# wisleep_revB.net
KiCad netlist of a schematic drawn in EAGLE
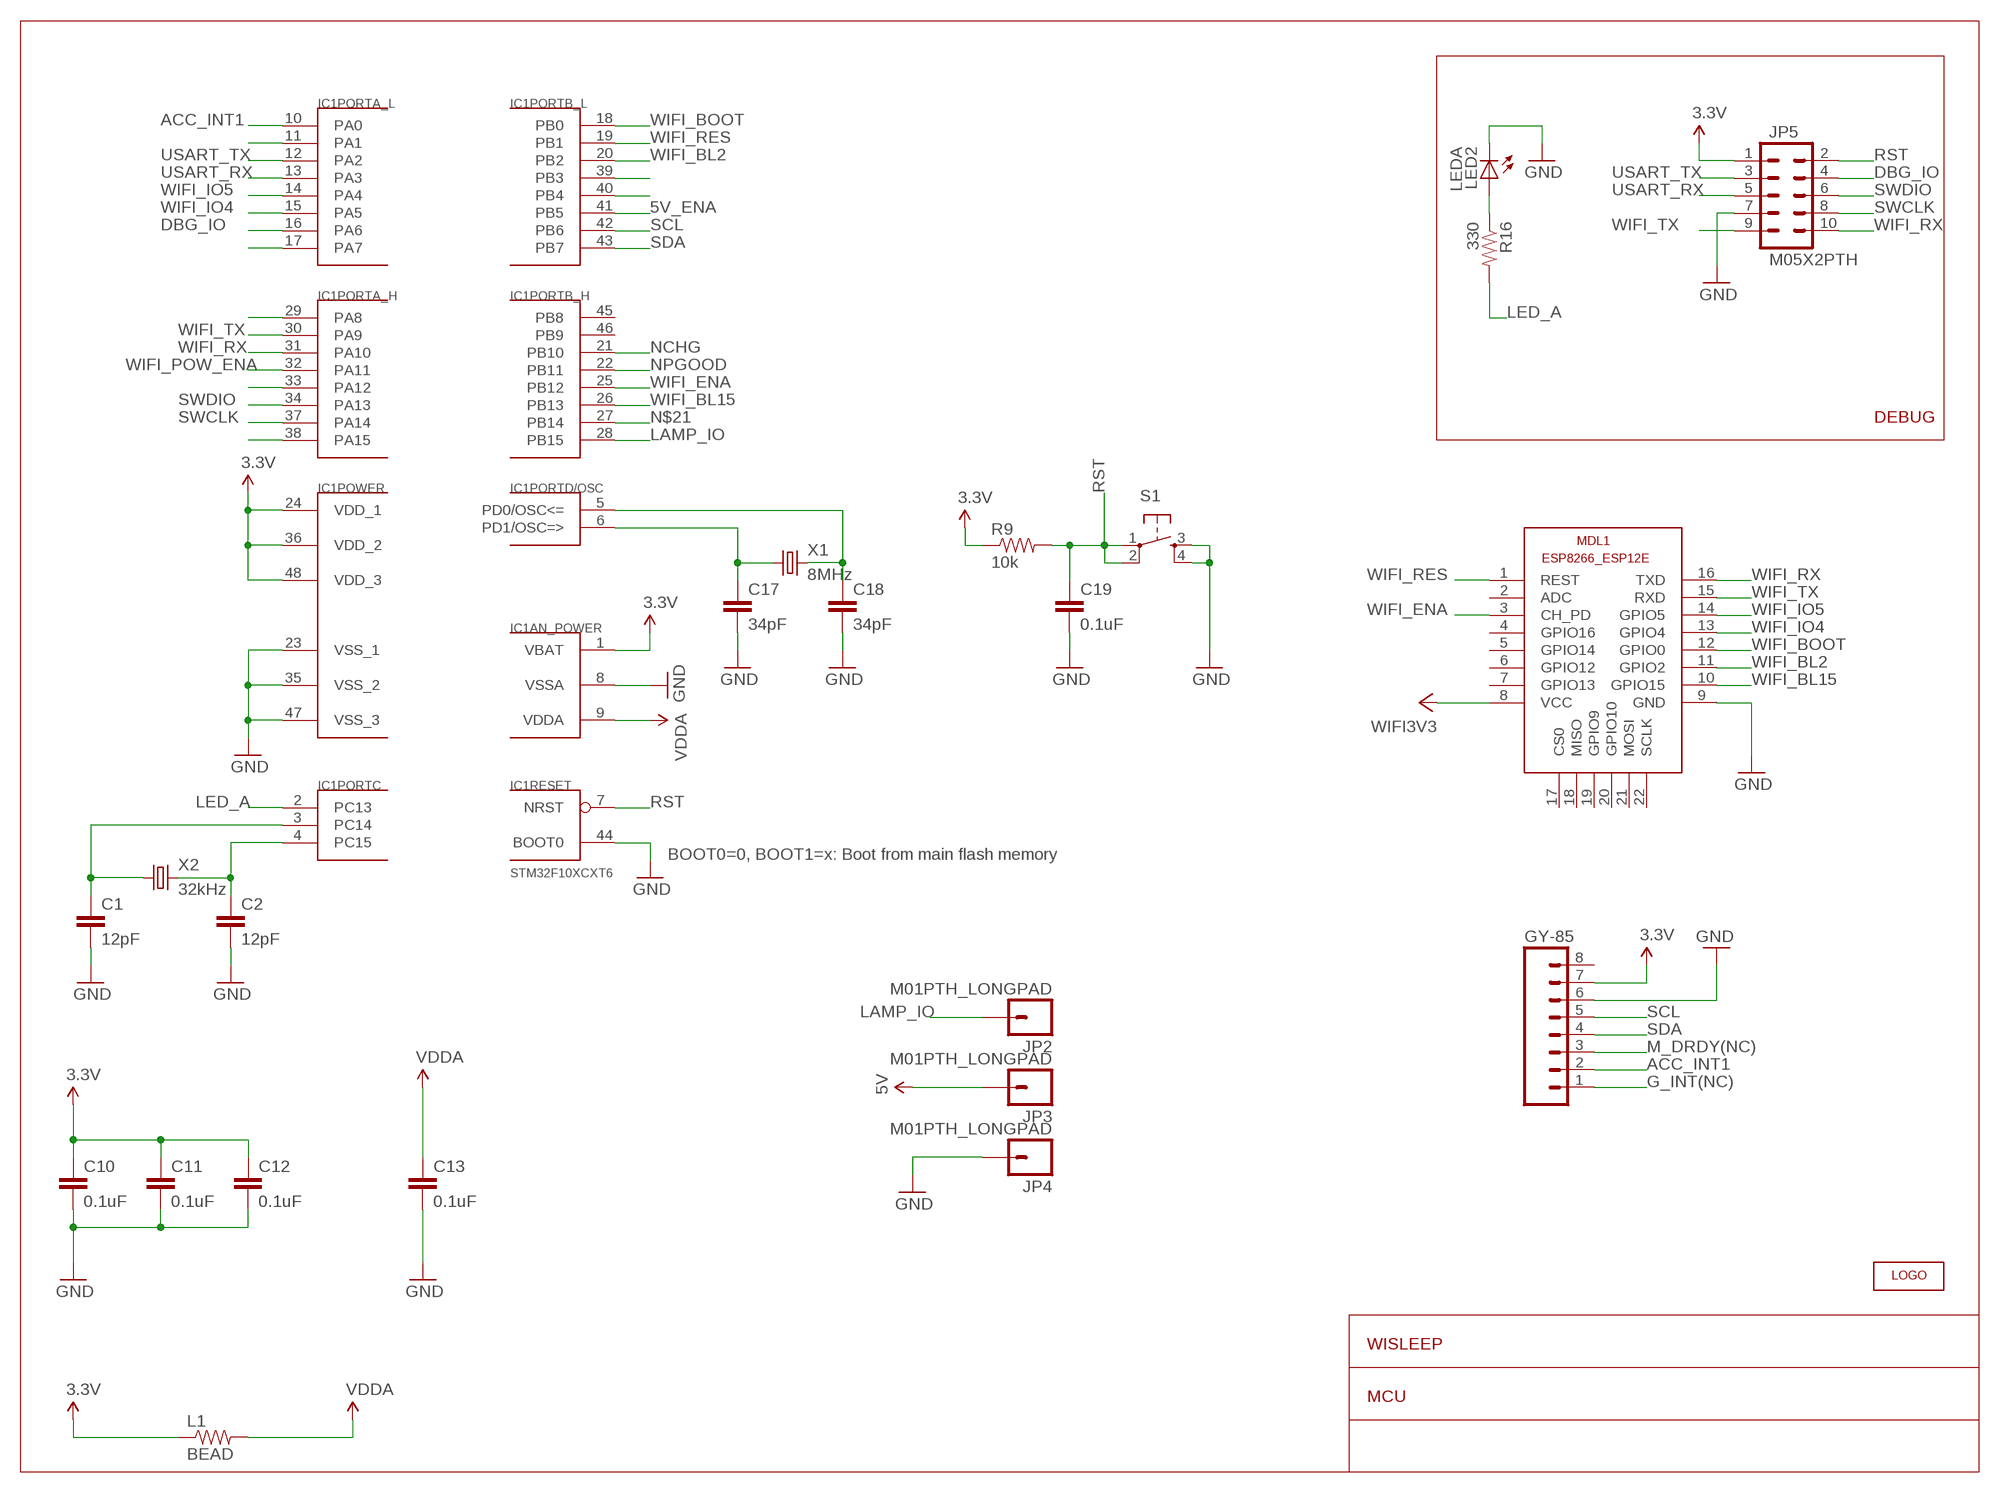
[diagram p0: schematic, sheet 1]
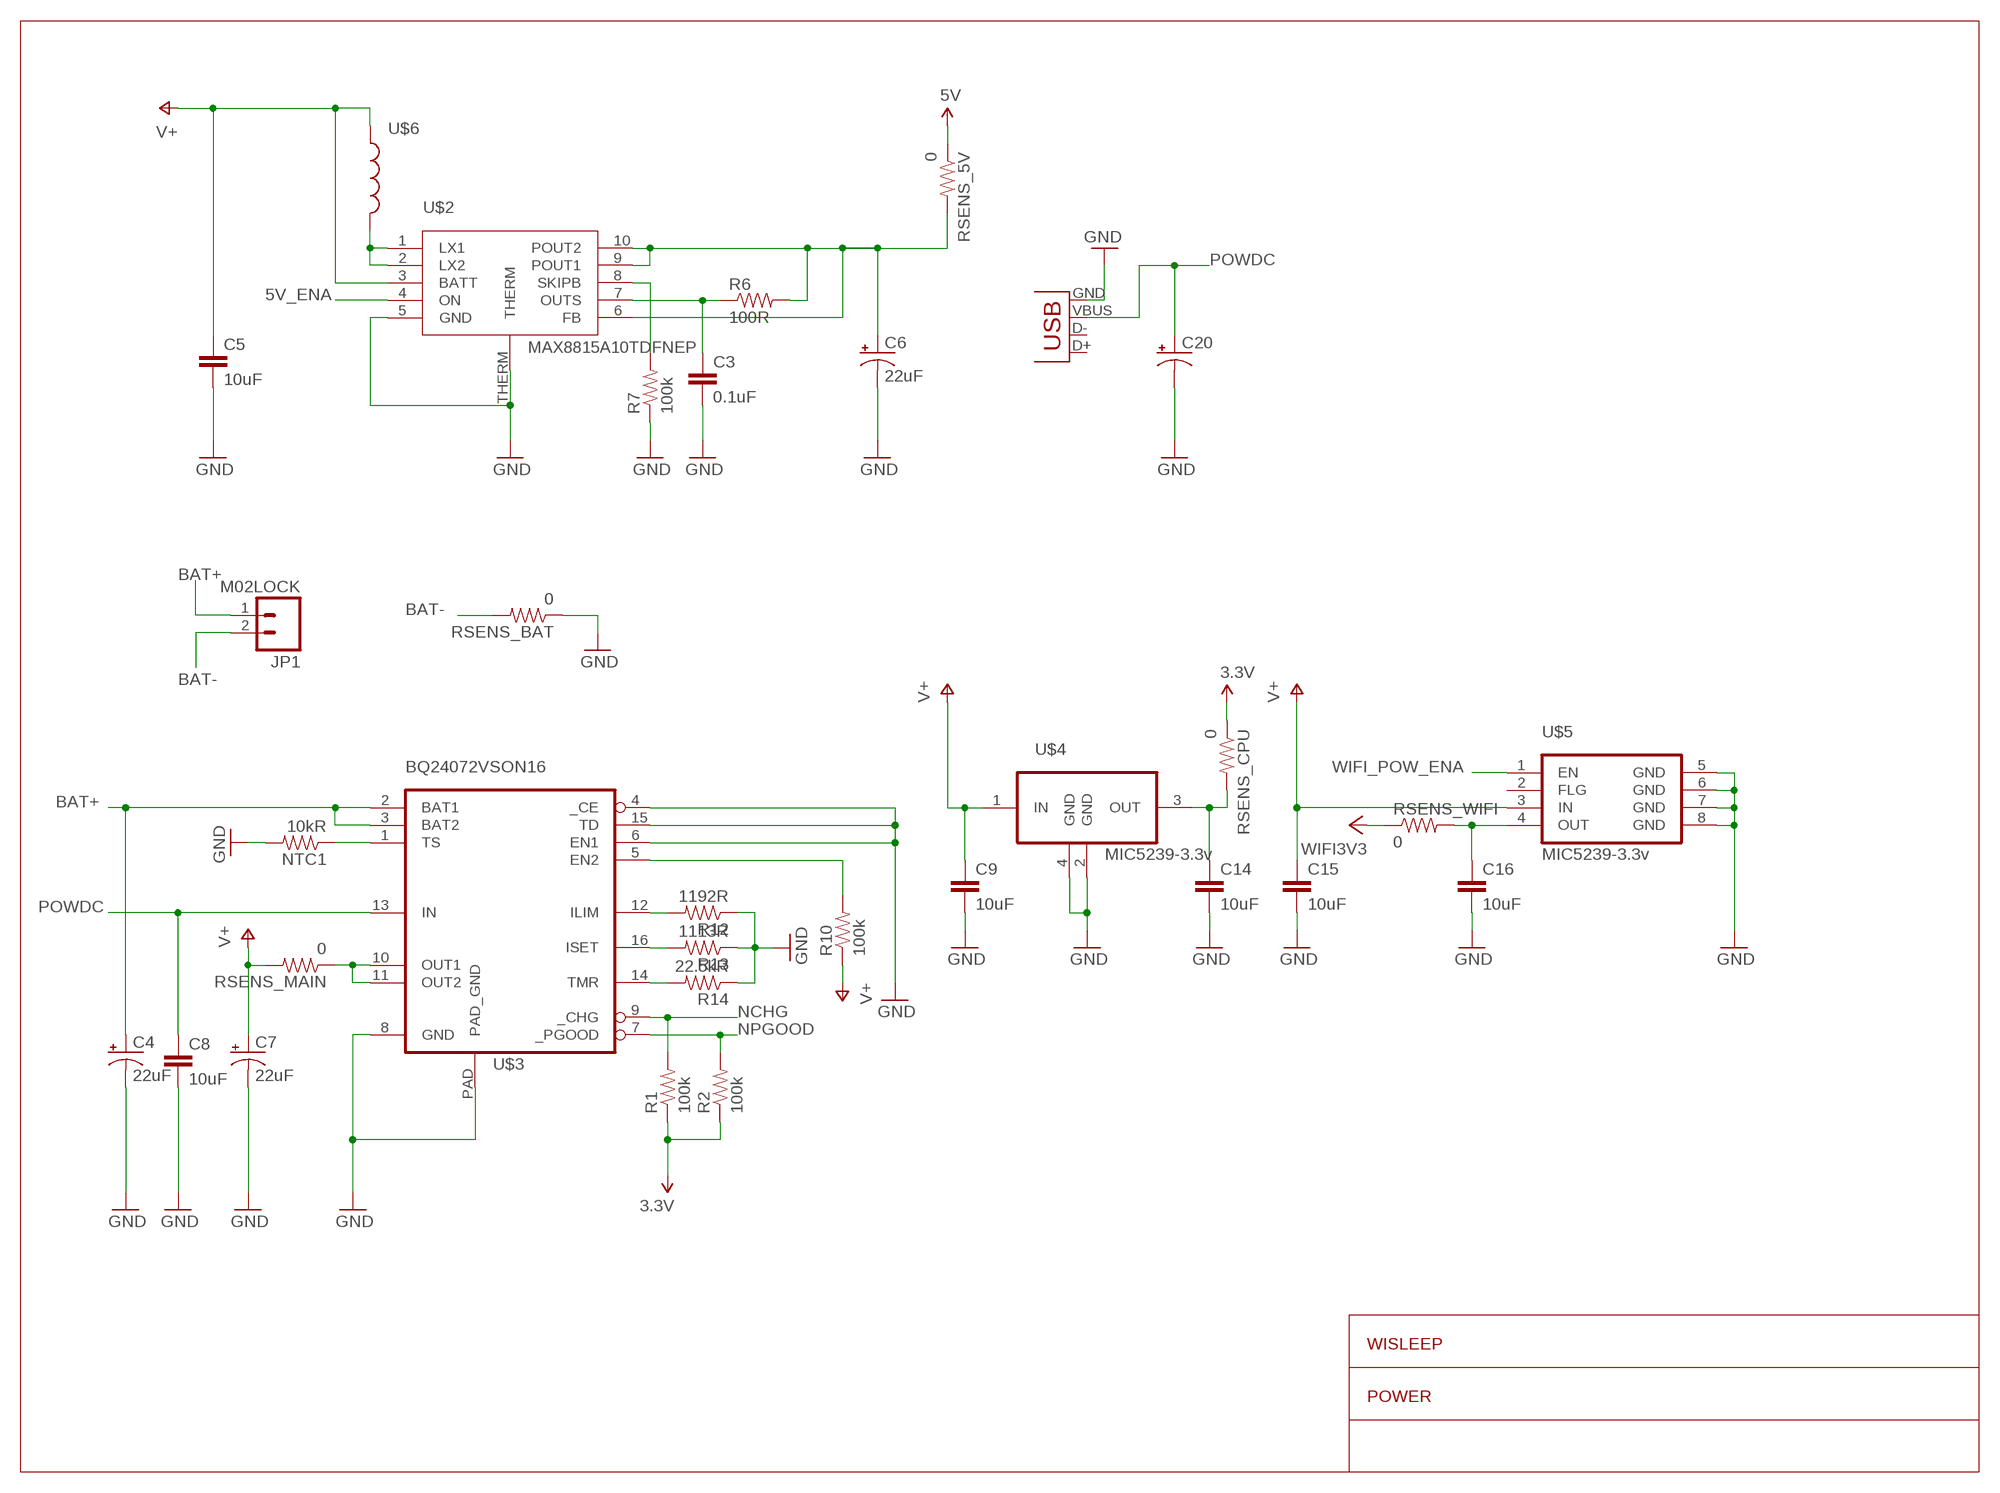
[diagram p1: schematic, sheet 2]

(export (version "E")
  (design (tool "Eeschema 10.0.6"))
  (components
    (comp (ref "C3")
      (value "0.1uF")
      (footprint "eagle-import:C0402")
      (libsource (lib "eagle-import") (part "CAP0402"))
    )
    (comp (ref "C4")
      (value "22uF")
      (footprint "eagle-import:EIA3216")
      (libsource (lib "eagle-import") (part "CAP_POL1206_CASE-A"))
    )
    (comp (ref "C5")
      (value "10uF")
      (footprint "eagle-import:C0402")
      (libsource (lib "eagle-import") (part "CAP0402"))
    )
    (comp (ref "C6")
      (value "22uF")
      (footprint "eagle-import:EIA3216")
      (libsource (lib "eagle-import") (part "CAP_POL1206_CASE-A"))
    )
    (comp (ref "C7")
      (value "22uF")
      (footprint "eagle-import:EIA3216")
      (libsource (lib "eagle-import") (part "CAP_POL1206_CASE-A"))
    )
    (comp (ref "C8")
      (value "10uF")
      (footprint "eagle-import:C0402")
      (libsource (lib "eagle-import") (part "CAP0402"))
    )
    (comp (ref "C9")
      (value "10uF")
      (footprint "eagle-import:C0402")
      (libsource (lib "eagle-import") (part "CAP0402"))
    )
    (comp (ref "C14")
      (value "10uF")
      (footprint "eagle-import:C0402")
      (libsource (lib "eagle-import") (part "CAP0402"))
    )
    (comp (ref "C15")
      (value "10uF")
      (footprint "eagle-import:C0402")
      (libsource (lib "eagle-import") (part "CAP0402"))
    )
    (comp (ref "C16")
      (value "10uF")
      (footprint "eagle-import:C0402")
      (libsource (lib "eagle-import") (part "CAP0402"))
    )
    (comp (ref "C20")
      (value "CAP_POL6032")
      (footprint "eagle-import:EIA6032")
      (libsource (lib "eagle-import") (part "CAP_POL6032"))
    )
    (comp (ref "JP1")
      (value "M02LOCK")
      (footprint "eagle-import:1X02_LOCK")
      (libsource (lib "eagle-import") (part "M02LOCK"))
    )
    (comp (ref "NTC1")
      (value "10kR")
      (footprint "eagle-import:C0402")
      (libsource (lib "eagle-import") (part "RESISTOR0402"))
    )
    (comp (ref "R1")
      (value "100k")
      (footprint "eagle-import:C0402")
      (libsource (lib "eagle-import") (part "RESISTOR0402"))
    )
    (comp (ref "R2")
      (value "100k")
      (footprint "eagle-import:C0402")
      (libsource (lib "eagle-import") (part "RESISTOR0402"))
    )
    (comp (ref "R6")
      (value "100R")
      (footprint "eagle-import:C0402")
      (libsource (lib "eagle-import") (part "RESISTOR0402"))
    )
    (comp (ref "R7")
      (value "100k")
      (footprint "eagle-import:C0402")
      (libsource (lib "eagle-import") (part "RESISTOR0402"))
    )
    (comp (ref "R10")
      (value "100k")
      (footprint "eagle-import:C0402")
      (libsource (lib "eagle-import") (part "RESISTOR0402"))
    )
    (comp (ref "R12")
      (value "1192R")
      (footprint "eagle-import:C0402")
      (libsource (lib "eagle-import") (part "RESISTOR0402"))
    )
    (comp (ref "R13")
      (value "1113R")
      (footprint "eagle-import:C0402")
      (libsource (lib "eagle-import") (part "RESISTOR0402"))
    )
    (comp (ref "R14")
      (value "22.5kR")
      (footprint "eagle-import:C0402")
      (libsource (lib "eagle-import") (part "RESISTOR0402"))
    )
    (comp (ref "RSENS_5V")
      (value "0")
      (footprint "eagle-import:C0402")
      (libsource (lib "eagle-import") (part "RESISTOR0402"))
    )
    (comp (ref "RSENS_BAT")
      (value "0")
      (footprint "eagle-import:C0402")
      (libsource (lib "eagle-import") (part "RESISTOR0402"))
    )
    (comp (ref "RSENS_CPU")
      (value "0")
      (footprint "eagle-import:C0402")
      (libsource (lib "eagle-import") (part "RESISTOR0402"))
    )
    (comp (ref "RSENS_MAIN")
      (value "0")
      (footprint "eagle-import:C0402")
      (libsource (lib "eagle-import") (part "RESISTOR0402"))
    )
    (comp (ref "RSENS_WIFI")
      (value "0")
      (footprint "eagle-import:C0402")
      (libsource (lib "eagle-import") (part "RESISTOR0402"))
    )
    (comp (ref "U$2")
      (value "MAX8815A10TDFNEP")
      (footprint "eagle-import:10-TDFN-EP")
      (libsource (lib "eagle-import") (part "MAX8815A10TDFNEP"))
    )
    (comp (ref "U$3")
      (value "BQ24072VSON16")
      (footprint "eagle-import:VSON16")
      (libsource (lib "eagle-import") (part "BQ24072VSON16"))
    )
    (comp (ref "U$4")
      (value "MIC5239-3.3v")
      (footprint "eagle-import:SOT223")
      (libsource (lib "eagle-import") (part "MIC5239SOT223SOT223"))
    )
    (comp (ref "U$5")
      (value "MIC5239-3.3v")
      (footprint "eagle-import:MSOP08")
      (libsource (lib "eagle-import") (part "MIC5239-8MSOP"))
    )
    (comp (ref "U$6")
      (value "INDUCTOR3014")
      (footprint "eagle-import:INDUCTOR-3014")
      (libsource (lib "eagle-import") (part "INDUCTOR3014"))
    )
    (comp (ref "X3")
      (value "USB-MINIB")
      (footprint "eagle-import:USB-MINIB")
      (libsource (lib "eagle-import") (part "USB-MINIB"))
    )
    (comp (ref "C1")
      (value "12pF")
      (footprint "eagle-import:C0402")
      (libsource (lib "eagle-import") (part "CAP0402"))
    )
    (comp (ref "C2")
      (value "12pF")
      (footprint "eagle-import:C0402")
      (libsource (lib "eagle-import") (part "CAP0402"))
    )
    (comp (ref "C10")
      (value "0.1uF")
      (footprint "eagle-import:C0402")
      (libsource (lib "eagle-import") (part "CAP0402"))
    )
    (comp (ref "C11")
      (value "0.1uF")
      (footprint "eagle-import:C0402")
      (libsource (lib "eagle-import") (part "CAP0402"))
    )
    (comp (ref "C12")
      (value "0.1uF")
      (footprint "eagle-import:C0402")
      (libsource (lib "eagle-import") (part "CAP0402"))
    )
    (comp (ref "C13")
      (value "0.1uF")
      (footprint "eagle-import:C0402")
      (libsource (lib "eagle-import") (part "CAP0402"))
    )
    (comp (ref "C17")
      (value "34pF")
      (footprint "eagle-import:C0402")
      (libsource (lib "eagle-import") (part "CAP0402"))
    )
    (comp (ref "C18")
      (value "34pF")
      (footprint "eagle-import:C0402")
      (libsource (lib "eagle-import") (part "CAP0402"))
    )
    (comp (ref "C19")
      (value "0.1uF")
      (footprint "eagle-import:C0402")
      (libsource (lib "eagle-import") (part "CAP0402"))
    )
    (comp (ref "GY-85")
      (value "M08")
      (footprint "eagle-import:1X08")
      (libsource (lib "eagle-import") (part "M08"))
    )
    (comp (ref "IC1")
      (value "STM32F10XCXT6")
      (footprint "eagle-import:TQFP48")
      (libsource (lib "eagle-import") (part "STM32F10XCXT6"))
    )
    (comp (ref "JP2")
      (value "M01PTH_LONGPAD")
      (footprint "eagle-import:1X01_LONGPAD")
      (libsource (lib "eagle-import") (part "M01PTH_LONGPAD"))
    )
    (comp (ref "JP3")
      (value "M01PTH_LONGPAD")
      (footprint "eagle-import:1X01_LONGPAD")
      (libsource (lib "eagle-import") (part "M01PTH_LONGPAD"))
    )
    (comp (ref "JP4")
      (value "M01PTH_LONGPAD")
      (footprint "eagle-import:1X01_LONGPAD")
      (libsource (lib "eagle-import") (part "M01PTH_LONGPAD"))
    )
    (comp (ref "JP5")
      (value "M05X2PTH")
      (footprint "eagle-import:AVR_ICSP")
      (libsource (lib "eagle-import") (part "M05X2PTH"))
    )
    (comp (ref "L1")
      (value "BEAD")
      (footprint "eagle-import:0603_GEN")
      (libsource (lib "eagle-import") (part "robot_RESISTOR0603"))
    )
    (comp (ref "LED2")
      (value "LEDA")
      (footprint "eagle-import:LED-0603")
      (libsource (lib "eagle-import") (part "LED0603"))
    )
    (comp (ref "MDL1")
      (value "ESP8266-12EESP8266-ESP12E")
      (footprint "eagle-import:ESP8266-ESP12E")
      (libsource (lib "eagle-import") (part "ESP8266-12EESP8266-ESP12E"))
    )
    (comp (ref "R9")
      (value "10k")
      (footprint "eagle-import:C0402")
      (libsource (lib "eagle-import") (part "RESISTOR0402"))
    )
    (comp (ref "R16")
      (value "330")
      (footprint "eagle-import:C0402")
      (libsource (lib "eagle-import") (part "RESISTOR0402"))
    )
    (comp (ref "S1")
      (value "TAC_SWITCHSMD")
      (footprint "eagle-import:TACTILE_SWITCH_SMD")
      (libsource (lib "eagle-import") (part "TAC_SWITCHSMD"))
    )
    (comp (ref "U$7")
      (value "LOGOLOGO")
      (footprint "eagle-import:LOGO")
      (libsource (lib "eagle-import") (part "LOGOLOGO"))
    )
    (comp (ref "X1")
      (value "8MHz")
      (footprint "eagle-import:CRYSTAL_SMD_5X3.2_7A")
      (libsource (lib "eagle-import") (part "CRYSTAL5X3.2_7AOWN"))
    )
    (comp (ref "X2")
      (value "32kHz")
      (footprint "eagle-import:CRYSTAL_SMD_2X0.6")
      (libsource (lib "eagle-import") (part "CRYSTAL"))
    )
  )
  (nets
    (net (code "1") (name "3.3V") (class "Default")
      (node (ref "C10") (pin "1") (pinfunction "1_1") (pintype "passive"))
      (node (ref "C11") (pin "1") (pinfunction "1_1") (pintype "passive"))
      (node (ref "C12") (pin "1") (pinfunction "1_1") (pintype "passive"))
      (node (ref "GY-85") (pin "7") (pinfunction "7_7") (pintype "passive"))
      (node (ref "IC1") (pin "1") (pinfunction "VBAT_1") (pintype "power_in"))
      (node (ref "IC1") (pin "24") (pinfunction "VDD_1_24") (pintype "power_in"))
      (node (ref "IC1") (pin "36") (pinfunction "VDD_2_36") (pintype "power_in"))
      (node (ref "IC1") (pin "48") (pinfunction "VDD_3_48") (pintype "power_in"))
      (node (ref "JP5") (pin "1") (pinfunction "1_1") (pintype "passive"))
      (node (ref "L1") (pin "1") (pinfunction "1_1") (pintype "passive"))
      (node (ref "R1") (pin "1") (pinfunction "1_1") (pintype "passive"))
      (node (ref "R2") (pin "1") (pinfunction "1_1") (pintype "passive"))
      (node (ref "R9") (pin "1") (pinfunction "1_1") (pintype "passive"))
      (node (ref "RSENS_CPU") (pin "1") (pinfunction "1_1") (pintype "passive"))
    )
    (net (code "2") (name "5V") (class "Default")
      (node (ref "JP3") (pin "1") (pinfunction "1_1") (pintype "passive"))
      (node (ref "RSENS_5V") (pin "1") (pinfunction "1_1") (pintype "passive"))
    )
    (net (code "3") (name "5V_ENA") (class "Default")
      (node (ref "IC1") (pin "41") (pinfunction "PB5_41") (pintype "bidirectional"))
      (node (ref "U$2") (pin "4") (pinfunction "ON_4") (pintype "input"))
    )
    (net (code "4") (name "ACC_INT1") (class "Default")
      (node (ref "GY-85") (pin "2") (pinfunction "2_2") (pintype "passive"))
      (node (ref "IC1") (pin "10") (pinfunction "PA0_10") (pintype "bidirectional"))
    )
    (net (code "5") (name "BAT+") (class "Default")
      (node (ref "C4") (pin "A") (pinfunction "+_A") (pintype "passive"))
      (node (ref "JP1") (pin "1") (pinfunction "1_1") (pintype "passive"))
      (node (ref "U$3") (pin "2") (pinfunction "BAT1_2") (pintype "power_in"))
      (node (ref "U$3") (pin "3") (pinfunction "BAT2_3") (pintype "power_in"))
    )
    (net (code "6") (name "BAT-") (class "Default")
      (node (ref "JP1") (pin "2") (pinfunction "2_2") (pintype "passive"))
      (node (ref "RSENS_BAT") (pin "2") (pinfunction "2_2") (pintype "passive"))
    )
    (net (code "7") (name "DBG_IO") (class "Default")
      (node (ref "IC1") (pin "16") (pinfunction "PA6_16") (pintype "bidirectional"))
      (node (ref "JP5") (pin "4") (pinfunction "4_4") (pintype "passive"))
    )
    (net (code "8") (name "GND") (class "Default")
      (node (ref "C1") (pin "2") (pinfunction "2_2") (pintype "passive"))
      (node (ref "C10") (pin "2") (pinfunction "2_2") (pintype "passive"))
      (node (ref "C11") (pin "2") (pinfunction "2_2") (pintype "passive"))
      (node (ref "C12") (pin "2") (pinfunction "2_2") (pintype "passive"))
      (node (ref "C13") (pin "2") (pinfunction "2_2") (pintype "passive"))
      (node (ref "C14") (pin "2") (pinfunction "2_2") (pintype "passive"))
      (node (ref "C15") (pin "2") (pinfunction "2_2") (pintype "passive"))
      (node (ref "C16") (pin "2") (pinfunction "2_2") (pintype "passive"))
      (node (ref "C17") (pin "2") (pinfunction "2_2") (pintype "passive"))
      (node (ref "C18") (pin "2") (pinfunction "2_2") (pintype "passive"))
      (node (ref "C19") (pin "2") (pinfunction "2_2") (pintype "passive"))
      (node (ref "C2") (pin "2") (pinfunction "2_2") (pintype "passive"))
      (node (ref "C20") (pin "P$2") (pinfunction "-_P$2") (pintype "passive"))
      (node (ref "C3") (pin "2") (pinfunction "2_2") (pintype "passive"))
      (node (ref "C4") (pin "C") (pinfunction "-_C") (pintype "passive"))
      (node (ref "C5") (pin "2") (pinfunction "2_2") (pintype "passive"))
      (node (ref "C6") (pin "C") (pinfunction "-_C") (pintype "passive"))
      (node (ref "C7") (pin "C") (pinfunction "-_C") (pintype "passive"))
      (node (ref "C8") (pin "2") (pinfunction "2_2") (pintype "passive"))
      (node (ref "C9") (pin "2") (pinfunction "2_2") (pintype "passive"))
      (node (ref "GY-85") (pin "6") (pinfunction "6_6") (pintype "passive"))
      (node (ref "IC1") (pin "23") (pinfunction "VSS_1_23") (pintype "power_in"))
      (node (ref "IC1") (pin "35") (pinfunction "VSS_2_35") (pintype "power_in"))
      (node (ref "IC1") (pin "44") (pinfunction "BOOT0_44") (pintype "input"))
      (node (ref "IC1") (pin "47") (pinfunction "VSS_3_47") (pintype "power_in"))
      (node (ref "IC1") (pin "8") (pinfunction "VSSA_8") (pintype "power_in"))
      (node (ref "JP4") (pin "1") (pinfunction "1_1") (pintype "passive"))
      (node (ref "JP5") (pin "7") (pinfunction "7_7") (pintype "passive"))
      (node (ref "LED2") (pin "C") (pinfunction "C_C") (pintype "passive"))
      (node (ref "MDL1") (pin "9") (pinfunction "GND_9") (pintype "bidirectional"))
      (node (ref "NTC1") (pin "2") (pinfunction "2_2") (pintype "passive"))
      (node (ref "R12") (pin "1") (pinfunction "1_1") (pintype "passive"))
      (node (ref "R13") (pin "1") (pinfunction "1_1") (pintype "passive"))
      (node (ref "R14") (pin "1") (pinfunction "1_1") (pintype "passive"))
      (node (ref "R7") (pin "1") (pinfunction "1_1") (pintype "passive"))
      (node (ref "RSENS_BAT") (pin "1") (pinfunction "1_1") (pintype "passive"))
      (node (ref "S1") (pin "3") (pinfunction "3_3") (pintype "passive"))
      (node (ref "S1") (pin "4") (pinfunction "4_4") (pintype "passive"))
      (node (ref "U$2") (pin "5") (pinfunction "GND_5") (pintype "power_in"))
      (node (ref "U$2") (pin "THERM") (pinfunction "THERM_THERM") (pintype "power_in"))
      (node (ref "U$3") (pin "15") (pinfunction "TD_15") (pintype "input"))
      (node (ref "U$3") (pin "4") (pinfunction "_CE_4") (pintype "input"))
      (node (ref "U$3") (pin "6") (pinfunction "EN1_6") (pintype "input"))
      (node (ref "U$3") (pin "8") (pinfunction "GND_8") (pintype "power_in"))
      (node (ref "U$3") (pin "PAD") (pinfunction "PAD_GND_PAD") (pintype "power_in"))
      (node (ref "U$4") (pin "2") (pinfunction "GND_2") (pintype "power_in"))
      (node (ref "U$4") (pin "4") (pinfunction "GND_4") (pintype "power_in"))
      (node (ref "U$5") (pin "5") (pinfunction "GND_5") (pintype "power_in"))
      (node (ref "U$5") (pin "6") (pinfunction "GND_6") (pintype "power_in"))
      (node (ref "U$5") (pin "7") (pinfunction "GND_7") (pintype "power_in"))
      (node (ref "U$5") (pin "8") (pinfunction "GND_8") (pintype "power_in"))
      (node (ref "X3") (pin "GND") (pinfunction "GND_GND") (pintype "bidirectional"))
    )
    (net (code "9") (name "G_INT(NC)") (class "Default")
      (node (ref "GY-85") (pin "1") (pinfunction "1_1") (pintype "passive"))
    )
    (net (code "10") (name "LAMP_IO") (class "Default")
      (node (ref "IC1") (pin "28") (pinfunction "PB15_28") (pintype "bidirectional"))
      (node (ref "JP2") (pin "1") (pinfunction "1_1") (pintype "passive"))
    )
    (net (code "11") (name "LED_A") (class "Default")
      (node (ref "IC1") (pin "2") (pinfunction "PC13_2") (pintype "bidirectional"))
      (node (ref "R16") (pin "2") (pinfunction "2_2") (pintype "passive"))
    )
    (net (code "12") (name "M_DRDY(NC)") (class "Default")
      (node (ref "GY-85") (pin "3") (pinfunction "3_3") (pintype "passive"))
    )
    (net (code "13") (name "N$21") (class "Default")
      (node (ref "IC1") (pin "27") (pinfunction "PB14_27") (pintype "bidirectional"))
    )
    (net (code "14") (name "NCHG") (class "Default")
      (node (ref "IC1") (pin "21") (pinfunction "PB10_21") (pintype "bidirectional"))
      (node (ref "R1") (pin "2") (pinfunction "2_2") (pintype "passive"))
      (node (ref "U$3") (pin "9") (pinfunction "_CHG_9") (pintype "output"))
    )
    (net (code "15") (name "NPGOOD") (class "Default")
      (node (ref "IC1") (pin "22") (pinfunction "PB11_22") (pintype "bidirectional"))
      (node (ref "R2") (pin "2") (pinfunction "2_2") (pintype "passive"))
      (node (ref "U$3") (pin "7") (pinfunction "_PGOOD_7") (pintype "output"))
    )
    (net (code "16") (name "Net-(C6-+)") (class "Default")
      (node (ref "C6") (pin "A") (pinfunction "+_A") (pintype "passive"))
      (node (ref "R6") (pin "2") (pinfunction "2_2") (pintype "passive"))
      (node (ref "RSENS_5V") (pin "2") (pinfunction "2_2") (pintype "passive"))
      (node (ref "U$2") (pin "10") (pinfunction "POUT2_10") (pintype "power_in"))
      (node (ref "U$2") (pin "6") (pinfunction "FB_6") (pintype "input"))
      (node (ref "U$2") (pin "9") (pinfunction "POUT1_9") (pintype "power_in"))
    )
    (net (code "17") (name "Net-(IC1F-PC14)") (class "Default")
      (node (ref "C1") (pin "1") (pinfunction "1_1") (pintype "passive"))
      (node (ref "IC1") (pin "3") (pinfunction "PC14_3") (pintype "bidirectional"))
      (node (ref "X2") (pin "P$1") (pinfunction "1_P$1") (pintype "passive"))
    )
    (net (code "18") (name "Net-(IC1F-PC15)") (class "Default")
      (node (ref "C2") (pin "1") (pinfunction "1_1") (pintype "passive"))
      (node (ref "IC1") (pin "4") (pinfunction "PC15_4") (pintype "bidirectional"))
      (node (ref "X2") (pin "P$2") (pinfunction "2_P$2") (pintype "passive"))
    )
    (net (code "19") (name "Net-(IC1G-PD0{slash}OSC<=)") (class "Default")
      (node (ref "C18") (pin "1") (pinfunction "1_1") (pintype "passive"))
      (node (ref "IC1") (pin "5") (pinfunction "PD0/OSC<=_5") (pintype "bidirectional"))
      (node (ref "X1") (pin "P$2") (pinfunction "2_P$2") (pintype "passive"))
    )
    (net (code "20") (name "Net-(IC1G-PD1{slash}OSC=>)") (class "Default")
      (node (ref "C17") (pin "1") (pinfunction "1_1") (pintype "passive"))
      (node (ref "IC1") (pin "6") (pinfunction "PD1/OSC=>_6") (pintype "bidirectional"))
      (node (ref "X1") (pin "P$1") (pinfunction "1_P$1") (pintype "passive"))
    )
    (net (code "21") (name "Net-(LED2-PadA)") (class "Default")
      (node (ref "LED2") (pin "A") (pinfunction "A_A") (pintype "passive"))
      (node (ref "R16") (pin "1") (pinfunction "1_1") (pintype "passive"))
    )
    (net (code "22") (name "Net-(U$2-LX1)") (class "Default")
      (node (ref "U$2") (pin "1") (pinfunction "LX1_1") (pintype "bidirectional"))
      (node (ref "U$2") (pin "2") (pinfunction "LX2_2") (pintype "bidirectional"))
      (node (ref "U$6") (pin "P$2") (pinfunction "2_P$2") (pintype "passive"))
    )
    (net (code "23") (name "Net-(U$2-OUTS)") (class "Default")
      (node (ref "C3") (pin "1") (pinfunction "1_1") (pintype "passive"))
      (node (ref "R6") (pin "1") (pinfunction "1_1") (pintype "passive"))
      (node (ref "U$2") (pin "7") (pinfunction "OUTS_7") (pintype "bidirectional"))
    )
    (net (code "24") (name "Net-(U$2-SKIPB)") (class "Default")
      (node (ref "R7") (pin "2") (pinfunction "2_2") (pintype "passive"))
      (node (ref "U$2") (pin "8") (pinfunction "SKIPB_8") (pintype "input"))
    )
    (net (code "25") (name "Net-(U$3-EN2)") (class "Default")
      (node (ref "R10") (pin "2") (pinfunction "2_2") (pintype "passive"))
      (node (ref "U$3") (pin "5") (pinfunction "EN2_5") (pintype "input"))
    )
    (net (code "26") (name "Net-(U$3-ILIM)") (class "Default")
      (node (ref "R12") (pin "2") (pinfunction "2_2") (pintype "passive"))
      (node (ref "U$3") (pin "12") (pinfunction "ILIM_12") (pintype "input"))
    )
    (net (code "27") (name "Net-(U$3-ISET)") (class "Default")
      (node (ref "R13") (pin "2") (pinfunction "2_2") (pintype "passive"))
      (node (ref "U$3") (pin "16") (pinfunction "ISET_16") (pintype "input"))
    )
    (net (code "28") (name "Net-(U$3-OUT1)") (class "Default")
      (node (ref "RSENS_MAIN") (pin "1") (pinfunction "1_1") (pintype "passive"))
      (node (ref "U$3") (pin "10") (pinfunction "OUT1_10") (pintype "power_in"))
      (node (ref "U$3") (pin "11") (pinfunction "OUT2_11") (pintype "power_in"))
    )
    (net (code "29") (name "Net-(U$3-TMR)") (class "Default")
      (node (ref "R14") (pin "2") (pinfunction "2_2") (pintype "passive"))
      (node (ref "U$3") (pin "14") (pinfunction "TMR_14") (pintype "input"))
    )
    (net (code "30") (name "Net-(U$3-TS)") (class "Default")
      (node (ref "NTC1") (pin "1") (pinfunction "1_1") (pintype "passive"))
      (node (ref "U$3") (pin "1") (pinfunction "TS_1") (pintype "bidirectional"))
    )
    (net (code "31") (name "Net-(U$4-OUT)") (class "Default")
      (node (ref "C14") (pin "1") (pinfunction "1_1") (pintype "passive"))
      (node (ref "RSENS_CPU") (pin "2") (pinfunction "2_2") (pintype "passive"))
      (node (ref "U$4") (pin "3") (pinfunction "OUT_3") (pintype "power_in"))
    )
    (net (code "32") (name "Net-(U$5-OUT)") (class "Default")
      (node (ref "C16") (pin "1") (pinfunction "1_1") (pintype "passive"))
      (node (ref "RSENS_WIFI") (pin "2") (pinfunction "2_2") (pintype "passive"))
      (node (ref "U$5") (pin "4") (pinfunction "OUT_4") (pintype "power_in"))
    )
    (net (code "33") (name "POWDC") (class "Default")
      (node (ref "C20") (pin "P$1") (pinfunction "+_P$1") (pintype "passive"))
      (node (ref "C8") (pin "1") (pinfunction "1_1") (pintype "passive"))
      (node (ref "U$3") (pin "13") (pinfunction "IN_13") (pintype "power_in"))
      (node (ref "X3") (pin "VBUS") (pinfunction "VBUS_VBUS") (pintype "bidirectional"))
    )
    (net (code "34") (name "RST") (class "Default")
      (node (ref "C19") (pin "1") (pinfunction "1_1") (pintype "passive"))
      (node (ref "IC1") (pin "7") (pinfunction "NRST_7") (pintype "input"))
      (node (ref "JP5") (pin "2") (pinfunction "2_2") (pintype "passive"))
      (node (ref "R9") (pin "2") (pinfunction "2_2") (pintype "passive"))
      (node (ref "S1") (pin "1") (pinfunction "1_1") (pintype "passive"))
      (node (ref "S1") (pin "2") (pinfunction "2_2") (pintype "passive"))
    )
    (net (code "35") (name "SCL") (class "Default")
      (node (ref "GY-85") (pin "5") (pinfunction "5_5") (pintype "passive"))
      (node (ref "IC1") (pin "42") (pinfunction "PB6_42") (pintype "bidirectional"))
    )
    (net (code "36") (name "SDA") (class "Default")
      (node (ref "GY-85") (pin "4") (pinfunction "4_4") (pintype "passive"))
      (node (ref "IC1") (pin "43") (pinfunction "PB7_43") (pintype "bidirectional"))
    )
    (net (code "37") (name "SWCLK") (class "Default")
      (node (ref "IC1") (pin "37") (pinfunction "PA14_37") (pintype "bidirectional"))
      (node (ref "JP5") (pin "8") (pinfunction "8_8") (pintype "passive"))
    )
    (net (code "38") (name "SWDIO") (class "Default")
      (node (ref "IC1") (pin "34") (pinfunction "PA13_34") (pintype "bidirectional"))
      (node (ref "JP5") (pin "6") (pinfunction "6_6") (pintype "passive"))
    )
    (net (code "39") (name "USART_RX") (class "Default")
      (node (ref "IC1") (pin "13") (pinfunction "PA3_13") (pintype "bidirectional"))
      (node (ref "JP5") (pin "5") (pinfunction "5_5") (pintype "passive"))
    )
    (net (code "40") (name "USART_TX") (class "Default")
      (node (ref "IC1") (pin "12") (pinfunction "PA2_12") (pintype "bidirectional"))
      (node (ref "JP5") (pin "3") (pinfunction "3_3") (pintype "passive"))
    )
    (net (code "41") (name "V+") (class "Default")
      (node (ref "C15") (pin "1") (pinfunction "1_1") (pintype "passive"))
      (node (ref "C5") (pin "1") (pinfunction "1_1") (pintype "passive"))
      (node (ref "C7") (pin "A") (pinfunction "+_A") (pintype "passive"))
      (node (ref "C9") (pin "1") (pinfunction "1_1") (pintype "passive"))
      (node (ref "R10") (pin "1") (pinfunction "1_1") (pintype "passive"))
      (node (ref "RSENS_MAIN") (pin "2") (pinfunction "2_2") (pintype "passive"))
      (node (ref "U$2") (pin "3") (pinfunction "BATT_3") (pintype "power_in"))
      (node (ref "U$4") (pin "1") (pinfunction "IN_1") (pintype "power_in"))
      (node (ref "U$5") (pin "3") (pinfunction "IN_3") (pintype "power_in"))
      (node (ref "U$6") (pin "P$1") (pinfunction "1_P$1") (pintype "passive"))
    )
    (net (code "42") (name "VCC") (class "Default")
      (node (ref "MDL1") (pin "8") (pinfunction "VCC_8") (pintype "bidirectional"))
      (node (ref "RSENS_WIFI") (pin "1") (pinfunction "1_1") (pintype "passive"))
    )
    (net (code "43") (name "VDDA") (class "Default")
      (node (ref "C13") (pin "1") (pinfunction "1_1") (pintype "passive"))
      (node (ref "IC1") (pin "9") (pinfunction "VDDA_9") (pintype "power_in"))
      (node (ref "L1") (pin "2") (pinfunction "2_2") (pintype "passive"))
    )
    (net (code "44") (name "WIFI_BL2") (class "Default")
      (node (ref "IC1") (pin "20") (pinfunction "PB2_20") (pintype "bidirectional"))
      (node (ref "MDL1") (pin "11") (pinfunction "GPIO2_11") (pintype "bidirectional"))
    )
    (net (code "45") (name "WIFI_BL15") (class "Default")
      (node (ref "IC1") (pin "26") (pinfunction "PB13_26") (pintype "bidirectional"))
      (node (ref "MDL1") (pin "10") (pinfunction "GPIO15_10") (pintype "bidirectional"))
    )
    (net (code "46") (name "WIFI_BOOT") (class "Default")
      (node (ref "IC1") (pin "18") (pinfunction "PB0_18") (pintype "bidirectional"))
      (node (ref "MDL1") (pin "12") (pinfunction "GPIO0_12") (pintype "bidirectional"))
    )
    (net (code "47") (name "WIFI_ENA") (class "Default")
      (node (ref "IC1") (pin "25") (pinfunction "PB12_25") (pintype "bidirectional"))
      (node (ref "MDL1") (pin "3") (pinfunction "CH_PD_3") (pintype "bidirectional"))
    )
    (net (code "48") (name "WIFI_IO4") (class "Default")
      (node (ref "IC1") (pin "15") (pinfunction "PA5_15") (pintype "bidirectional"))
      (node (ref "MDL1") (pin "13") (pinfunction "GPIO4_13") (pintype "bidirectional"))
    )
    (net (code "49") (name "WIFI_IO5") (class "Default")
      (node (ref "IC1") (pin "14") (pinfunction "PA4_14") (pintype "bidirectional"))
      (node (ref "MDL1") (pin "14") (pinfunction "GPIO5_14") (pintype "bidirectional"))
    )
    (net (code "50") (name "WIFI_POW_ENA") (class "Default")
      (node (ref "IC1") (pin "32") (pinfunction "PA11_32") (pintype "bidirectional"))
      (node (ref "U$5") (pin "1") (pinfunction "EN_1") (pintype "input"))
    )
    (net (code "51") (name "WIFI_RES") (class "Default")
      (node (ref "IC1") (pin "19") (pinfunction "PB1_19") (pintype "bidirectional"))
      (node (ref "MDL1") (pin "1") (pinfunction "REST_1") (pintype "bidirectional"))
    )
    (net (code "52") (name "WIFI_RX") (class "Default")
      (node (ref "IC1") (pin "31") (pinfunction "PA10_31") (pintype "bidirectional"))
      (node (ref "JP5") (pin "10") (pinfunction "10_10") (pintype "passive"))
      (node (ref "MDL1") (pin "16") (pinfunction "TXD_16") (pintype "bidirectional"))
    )
    (net (code "53") (name "WIFI_TX") (class "Default")
      (node (ref "IC1") (pin "30") (pinfunction "PA9_30") (pintype "bidirectional"))
      (node (ref "JP5") (pin "9") (pinfunction "9_9") (pintype "passive"))
      (node (ref "MDL1") (pin "15") (pinfunction "RXD_15") (pintype "bidirectional"))
    )
    (net (code "54") (name "unconnected-(GY-85-Pad8)") (class "Default")
      (node (ref "GY-85") (pin "8") (pinfunction "8_8") (pintype "passive"))
    )
    (net (code "55") (name "unconnected-(IC1B-PA8-Pad29)") (class "Default")
      (node (ref "IC1") (pin "29") (pinfunction "PA8_29") (pintype "bidirectional"))
    )
    (net (code "56") (name "unconnected-(IC1B-PA12-Pad33)") (class "Default")
      (node (ref "IC1") (pin "33") (pinfunction "PA12_33") (pintype "bidirectional"))
    )
    (net (code "57") (name "unconnected-(IC1B-PA15-Pad38)") (class "Default")
      (node (ref "IC1") (pin "38") (pinfunction "PA15_38") (pintype "bidirectional"))
    )
    (net (code "58") (name "unconnected-(IC1C-PA1-Pad11)") (class "Default")
      (node (ref "IC1") (pin "11") (pinfunction "PA1_11") (pintype "bidirectional"))
    )
    (net (code "59") (name "unconnected-(IC1C-PA7-Pad17)") (class "Default")
      (node (ref "IC1") (pin "17") (pinfunction "PA7_17") (pintype "bidirectional"))
    )
    (net (code "60") (name "unconnected-(IC1D-PB8-Pad45)") (class "Default")
      (node (ref "IC1") (pin "45") (pinfunction "PB8_45") (pintype "bidirectional"))
    )
    (net (code "61") (name "unconnected-(IC1D-PB9-Pad46)") (class "Default")
      (node (ref "IC1") (pin "46") (pinfunction "PB9_46") (pintype "bidirectional"))
    )
    (net (code "62") (name "unconnected-(IC1E-PB3-Pad39)") (class "Default")
      (node (ref "IC1") (pin "39") (pinfunction "PB3_39") (pintype "bidirectional"))
    )
    (net (code "63") (name "unconnected-(IC1E-PB4-Pad40)") (class "Default")
      (node (ref "IC1") (pin "40") (pinfunction "PB4_40") (pintype "bidirectional"))
    )
    (net (code "64") (name "unconnected-(MDL1-ADC-Pad2)") (class "Default")
      (node (ref "MDL1") (pin "2") (pinfunction "ADC_2") (pintype "bidirectional"))
    )
    (net (code "65") (name "unconnected-(MDL1-CS0-Pad17)") (class "Default")
      (node (ref "MDL1") (pin "17") (pinfunction "CS0_17") (pintype "bidirectional"))
    )
    (net (code "66") (name "unconnected-(MDL1-GPIO9-Pad19)") (class "Default")
      (node (ref "MDL1") (pin "19") (pinfunction "GPIO9_19") (pintype "bidirectional"))
    )
    (net (code "67") (name "unconnected-(MDL1-GPIO10-Pad20)") (class "Default")
      (node (ref "MDL1") (pin "20") (pinfunction "GPIO10_20") (pintype "bidirectional"))
    )
    (net (code "68") (name "unconnected-(MDL1-GPIO12-Pad6)") (class "Default")
      (node (ref "MDL1") (pin "6") (pinfunction "GPIO12_6") (pintype "bidirectional"))
    )
    (net (code "69") (name "unconnected-(MDL1-GPIO13-Pad7)") (class "Default")
      (node (ref "MDL1") (pin "7") (pinfunction "GPIO13_7") (pintype "bidirectional"))
    )
    (net (code "70") (name "unconnected-(MDL1-GPIO14-Pad5)") (class "Default")
      (node (ref "MDL1") (pin "5") (pinfunction "GPIO14_5") (pintype "bidirectional"))
    )
    (net (code "71") (name "unconnected-(MDL1-GPIO16-Pad4)") (class "Default")
      (node (ref "MDL1") (pin "4") (pinfunction "GPIO16_4") (pintype "bidirectional"))
    )
    (net (code "72") (name "unconnected-(MDL1-MISO-Pad18)") (class "Default")
      (node (ref "MDL1") (pin "18") (pinfunction "MISO_18") (pintype "bidirectional"))
    )
    (net (code "73") (name "unconnected-(MDL1-MOSI-Pad21)") (class "Default")
      (node (ref "MDL1") (pin "21") (pinfunction "MOSI_21") (pintype "bidirectional"))
    )
    (net (code "74") (name "unconnected-(MDL1-SCLK-Pad22)") (class "Default")
      (node (ref "MDL1") (pin "22") (pinfunction "SCLK_22") (pintype "bidirectional"))
    )
    (net (code "75") (name "unconnected-(U$5-FLG-Pad2)") (class "Default")
      (node (ref "U$5") (pin "2") (pinfunction "FLG_2") (pintype "output"))
    )
    (net (code "76") (name "unconnected-(X3-PadD+)") (class "Default")
      (node (ref "X3") (pin "D+") (pinfunction "D+_D+") (pintype "bidirectional"))
    )
    (net (code "77") (name "unconnected-(X3-PadD-)") (class "Default")
      (node (ref "X3") (pin "D-") (pinfunction "D-_D-") (pintype "bidirectional"))
    )
  )
)
